# adjustable_biasing_with_jumper.net
KiCad netlist of a schematic drawn in Altium Designer
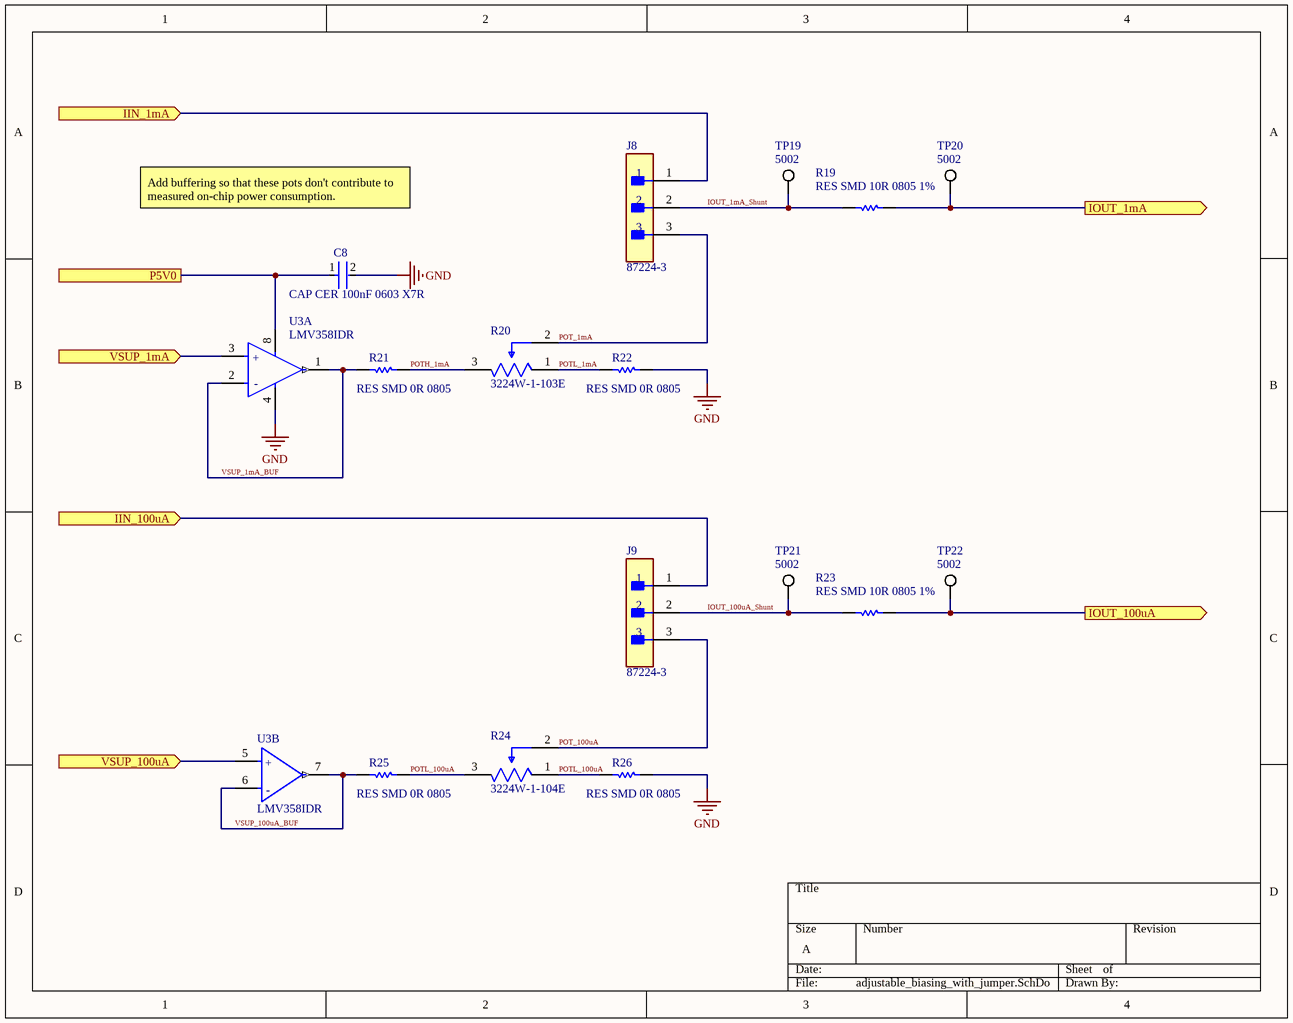
[diagram p0: adjustable_biasing_with_jumper.SchDoc]

(export (version "E")
  (design (tool "Eeschema 10.0.6"))
  (components
    (comp (ref "C8")
      (value "CAP CER 100nF 0603 X7R")
      (footprint "FP-CC0603-DA-MFG")
      (description "CAP CER 0.1UF 16V X7R 0603")
      (fields
        (field (name "OCTOPART") "https://octopart.com/cc0603krx7r7bb104-yageo-192941")
        (field (name "TOLERANCE") "0.1")
      )
      (libsource (lib "Altium Content Vault") (part "11868f565c42a9108669ba33697ecf6"))
    )
    (comp (ref "J8")
      (value "87224-3")
      (footprint "FP-87224-3-MFG")
      (description "CONN HEADER VERT 3POS 2.54MM")
      (libsource (lib "Altium Content Vault") (part "0d3f023dd272f625e17a2be33dea85f"))
    )
    (comp (ref "J9")
      (value "87224-3")
      (footprint "FP-87224-3-MFG")
      (description "CONN HEADER VERT 3POS 2.54MM")
      (libsource (lib "Altium Content Vault") (part "0d3f023dd272f625e17a2be33dea85f"))
    )
    (comp (ref "R19")
      (value "RES SMD 10R 0805 1%")
      (footprint "RESC2013X55X40NL15T20")
      (fields (field (name "MANUFACTURER") "Vishay Dale") (field (name "PART NUMBER") "TNPW0805100RBEEA"))
      (libsource (lib "Altium Content Vault") (part "RES"))
    )
    (comp (ref "R20")
      (value "3224W-1-103E")
      (footprint "FP-3224W-MFG")
      (description "TRIMMER 10K OHM 0.25W J LEAD TOP")
      (fields (field (name "TOLERANCE") "10%") (field (name "MANUFACTURER") "Bourns"))
      (libsource (lib "Altium Content Vault") (part "83d3d349ed884d1db45cec512f27eb6"))
    )
    (comp (ref "R21")
      (value "RES SMD 0R 0805")
      (footprint "RESC2013X55X40NL15T20")
      (fields (field (name "MANUFACTURER") "Vishay Dale") (field (name "PART NUMBER") "TNPW0805100RBEEA"))
      (libsource (lib "Altium Content Vault") (part "RES"))
    )
    (comp (ref "R22")
      (value "RES SMD 0R 0805")
      (footprint "RESC2013X55X40NL15T20")
      (fields (field (name "MANUFACTURER") "Vishay Dale") (field (name "PART NUMBER") "TNPW0805100RBEEA"))
      (libsource (lib "Altium Content Vault") (part "RES"))
    )
    (comp (ref "R23")
      (value "RES SMD 10R 0805 1%")
      (footprint "RESC2013X55X40NL15T20")
      (fields (field (name "MANUFACTURER") "Vishay Dale") (field (name "PART NUMBER") "TNPW0805100RBEEA"))
      (libsource (lib "Altium Content Vault") (part "RES"))
    )
    (comp (ref "R24")
      (value "3224W-1-104E")
      (footprint "FP-3224W-MFG")
      (description "TRIMMER 10K OHM 0.25W J LEAD TOP")
      (fields (field (name "TOLERANCE") "10%") (field (name "MANUFACTURER") "Bourns"))
      (libsource (lib "Altium Content Vault") (part "83d3d349ed884d1db45cec512f27eb6"))
    )
    (comp (ref "R25")
      (value "RES SMD 0R 0805")
      (footprint "RESC2013X55X40NL15T20")
      (fields (field (name "MANUFACTURER") "Vishay Dale") (field (name "PART NUMBER") "TNPW0805100RBEEA"))
      (libsource (lib "Altium Content Vault") (part "RES"))
    )
    (comp (ref "R26")
      (value "RES SMD 0R 0805")
      (footprint "RESC2013X55X40NL15T20")
      (fields (field (name "MANUFACTURER") "Vishay Dale") (field (name "PART NUMBER") "TNPW0805100RBEEA"))
      (libsource (lib "Altium Content Vault") (part "RES"))
    )
    (comp (ref "TP19")
      (value "5002")
      (footprint "KSTN-5002")
      (description "Test Point, White, 1-Pin THD, RoHS, Bulk")
      (fields (field (name "MANUFACTURER") "KeystoneElectronics"))
      (libsource (lib "Altium Content Vault") (part "KSTN-TP-5002"))
    )
    (comp (ref "TP20")
      (value "5002")
      (footprint "KSTN-5002")
      (description "Test Point, White, 1-Pin THD, RoHS, Bulk")
      (fields (field (name "MANUFACTURER") "KeystoneElectronics"))
      (libsource (lib "Altium Content Vault") (part "KSTN-TP-5002"))
    )
    (comp (ref "TP21")
      (value "5002")
      (footprint "KSTN-5002")
      (description "Test Point, White, 1-Pin THD, RoHS, Bulk")
      (fields (field (name "MANUFACTURER") "KeystoneElectronics"))
      (libsource (lib "Altium Content Vault") (part "KSTN-TP-5002"))
    )
    (comp (ref "TP22")
      (value "5002")
      (footprint "KSTN-5002")
      (description "Test Point, White, 1-Pin THD, RoHS, Bulk")
      (fields (field (name "MANUFACTURER") "KeystoneElectronics"))
      (libsource (lib "Altium Content Vault") (part "KSTN-TP-5002"))
    )
    (comp (ref "U3")
      (value "LMV358IDR")
      (footprint "FP-D0008A-MFG")
      (description "IC OPAMP GP 2 CIRCUIT 8SOIC")
      (libsource (lib "Altium Content Vault") (part "1f85fec4e6914445158f776dbf16c1d"))
    )
  )
  (nets
    (net (code "1") (name "/IIN_1mA") (class "Default")
      (node (ref "J8") (pin "1") (pinfunction "1_1") (pintype "passive"))
    )
    (net (code "2") (name "/IIN_100uA") (class "Default")
      (node (ref "J9") (pin "1") (pinfunction "1_1") (pintype "passive"))
    )
    (net (code "3") (name "/IOUT_1mA") (class "Default")
      (node (ref "R19") (pin "2") (pinfunction "2_2") (pintype "passive"))
      (node (ref "TP20") (pin "1") (pintype "passive"))
    )
    (net (code "4") (name "/IOUT_1mA_Shunt") (class "Default")
      (node (ref "J8") (pin "2") (pinfunction "2_2") (pintype "passive"))
      (node (ref "R19") (pin "1") (pinfunction "1_1") (pintype "passive"))
      (node (ref "TP19") (pin "1") (pintype "passive"))
    )
    (net (code "5") (name "/IOUT_100uA") (class "Default")
      (node (ref "R23") (pin "2") (pinfunction "2_2") (pintype "passive"))
      (node (ref "TP22") (pin "1") (pintype "passive"))
    )
    (net (code "6") (name "/IOUT_100uA_Shunt") (class "Default")
      (node (ref "J9") (pin "2") (pinfunction "2_2") (pintype "passive"))
      (node (ref "R23") (pin "1") (pinfunction "1_1") (pintype "passive"))
      (node (ref "TP21") (pin "1") (pintype "passive"))
    )
    (net (code "7") (name "/P5V0") (class "Default")
      (node (ref "C8") (pin "1") (pinfunction "1_1") (pintype "passive"))
      (node (ref "U3") (pin "8") (pinfunction "VCC+_8") (pintype "power_in"))
    )
    (net (code "8") (name "/POTH_1mA") (class "Default")
      (node (ref "R20") (pin "3") (pinfunction "CW_3") (pintype "passive"))
      (node (ref "R21") (pin "2") (pinfunction "2_2") (pintype "passive"))
    )
    (net (code "9") (name "/POTL_1mA") (class "Default")
      (node (ref "R20") (pin "1") (pinfunction "CCW_1") (pintype "passive"))
      (node (ref "R22") (pin "1") (pinfunction "1_1") (pintype "passive"))
    )
    (net (code "10") (name "/POTL_100uA") (class "Default")
      (node (ref "R24") (pin "1") (pinfunction "CCW_1") (pintype "passive"))
      (node (ref "R24") (pin "3") (pinfunction "CW_3") (pintype "passive"))
      (node (ref "R25") (pin "2") (pinfunction "2_2") (pintype "passive"))
      (node (ref "R26") (pin "1") (pinfunction "1_1") (pintype "passive"))
    )
    (net (code "11") (name "/POT_1mA") (class "Default")
      (node (ref "J8") (pin "3") (pinfunction "3_3") (pintype "passive"))
      (node (ref "R20") (pin "2") (pinfunction "WIPER_2") (pintype "passive"))
    )
    (net (code "12") (name "/POT_100uA") (class "Default")
      (node (ref "J9") (pin "3") (pinfunction "3_3") (pintype "passive"))
      (node (ref "R24") (pin "2") (pinfunction "WIPER_2") (pintype "passive"))
    )
    (net (code "13") (name "/VSUP_1mA") (class "Default")
      (node (ref "U3") (pin "3") (pinfunction "1IN+_3") (pintype "tri_state"))
    )
    (net (code "14") (name "/VSUP_1mA_BUF") (class "Default")
      (node (ref "R21") (pin "1") (pinfunction "1_1") (pintype "passive"))
      (node (ref "U3") (pin "1") (pinfunction "OUT_1") (pintype "output"))
      (node (ref "U3") (pin "2") (pinfunction "1IN-_2") (pintype "tri_state"))
    )
    (net (code "15") (name "/VSUP_100uA") (class "Default")
      (node (ref "U3") (pin "5") (pinfunction "2IN+_5") (pintype "tri_state"))
    )
    (net (code "16") (name "/VSUP_100uA_BUF") (class "Default")
      (node (ref "R25") (pin "1") (pinfunction "1_1") (pintype "passive"))
      (node (ref "U3") (pin "6") (pinfunction "2IN-_6") (pintype "tri_state"))
      (node (ref "U3") (pin "7") (pinfunction "2OUT_7") (pintype "output"))
    )
    (net (code "17") (name "GND") (class "Default")
      (node (ref "C8") (pin "2") (pinfunction "2_2") (pintype "passive"))
      (node (ref "R22") (pin "2") (pinfunction "2_2") (pintype "passive"))
      (node (ref "R26") (pin "2") (pinfunction "2_2") (pintype "passive"))
      (node (ref "U3") (pin "4") (pinfunction "GND_4") (pintype "power_in"))
    )
  )
)
